# DualBalancedInput.net
KiCad netlist of a schematic drawn in EAGLE
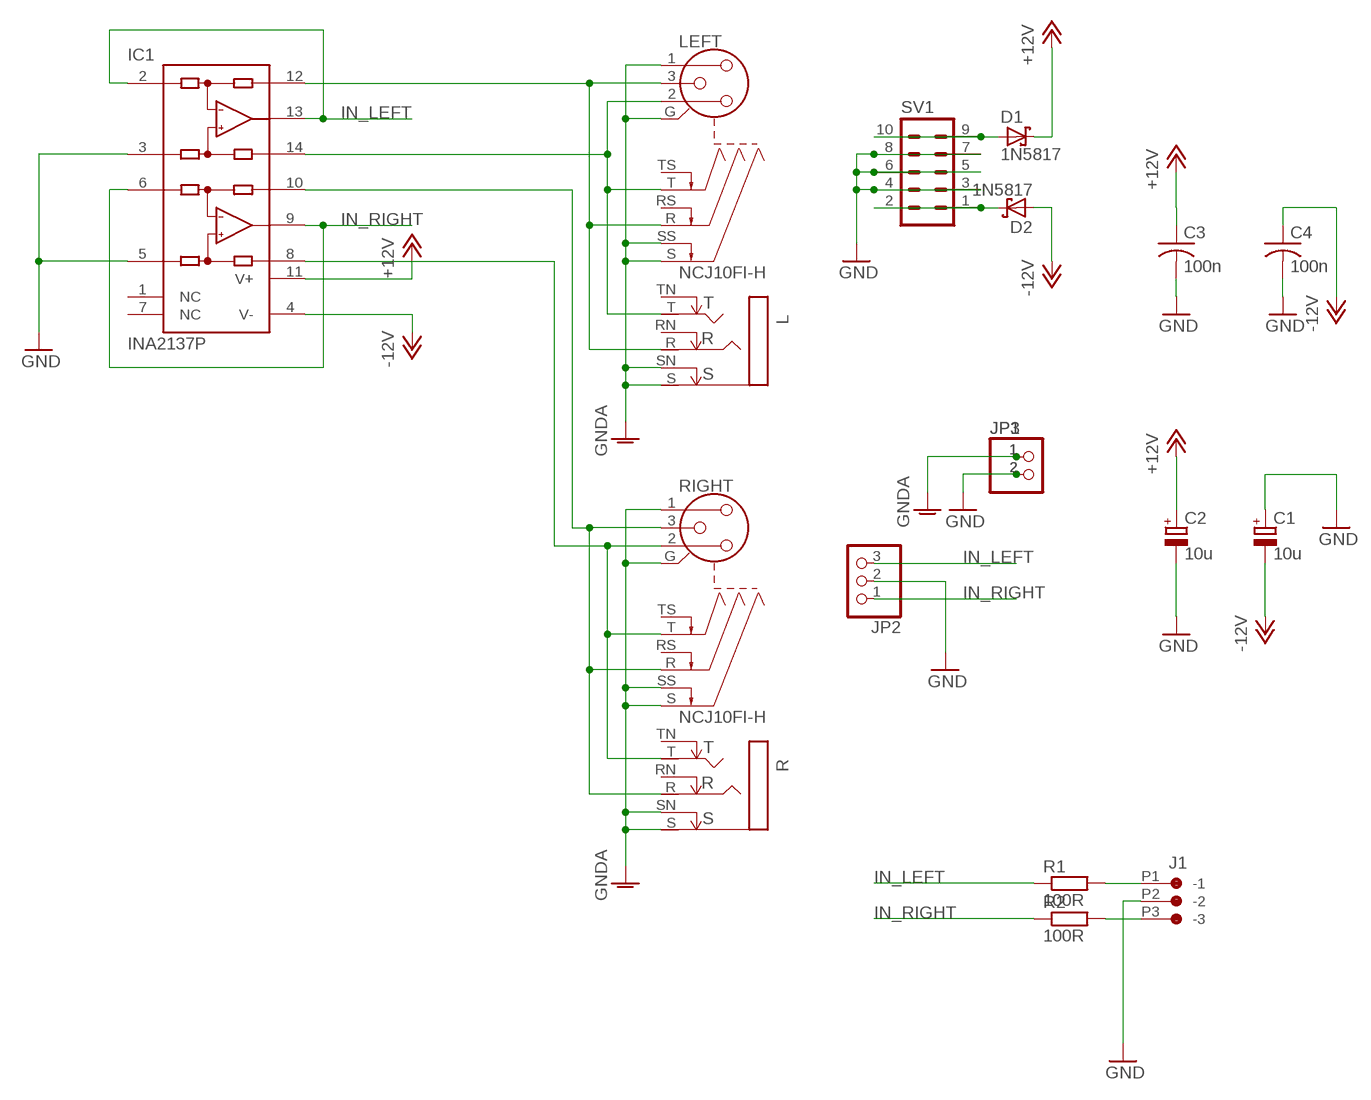
[diagram p0: schematic, sheet 1]

(export (version "E")
  (design (tool "Eeschema 10.0.6"))
  (components
    (comp (ref "C1")
      (value "10u")
      (footprint "eagle-import:E5-6")
      (libsource (lib "eagle-import") (part "CPOL-EUE5-6"))
    )
    (comp (ref "C2")
      (value "10u")
      (footprint "eagle-import:E5-6")
      (libsource (lib "eagle-import") (part "CPOL-EUE5-6"))
    )
    (comp (ref "C3")
      (value "100n")
      (footprint "eagle-import:C050-024X044")
      (libsource (lib "eagle-import") (part "C-US050-024X044"))
    )
    (comp (ref "C4")
      (value "100n")
      (footprint "eagle-import:C050-024X044")
      (libsource (lib "eagle-import") (part "C-US050-024X044"))
    )
    (comp (ref "D1")
      (value "1N5817")
      (footprint "eagle-import:DO41-7.6")
      (libsource (lib "eagle-import") (part "1N5819-B"))
    )
    (comp (ref "D2")
      (value "1N5817")
      (footprint "eagle-import:DO41-7.6")
      (libsource (lib "eagle-import") (part "1N5819-B"))
    )
    (comp (ref "IC1")
      (value "INA2137P")
      (footprint "eagle-import:DIL14")
      (fields (field (name "MF") "TEXAS INSTRUMENT CONNECTORS") (field (name "MPN") "INA2137PA"))
      (libsource (lib "eagle-import") (part "INA2137P"))
    )
    (comp (ref "J1")
      (value "CON-JST_PH_3W")
      (footprint "eagle-import:CON-JST_PH_3W")
      (libsource (lib "eagle-import") (part "CON-JST_PH_3W"))
    )
    (comp (ref "JP1")
      (value "PINHD-1X2")
      (footprint "eagle-import:1X02")
      (libsource (lib "eagle-import") (part "PINHD-1X2"))
    )
    (comp (ref "JP2")
      (value "PINHD-1X3")
      (footprint "eagle-import:1X03")
      (libsource (lib "eagle-import") (part "PINHD-1X3"))
    )
    (comp (ref "JP3")
      (value "PINHD-1X2")
      (footprint "eagle-import:1X02")
      (libsource (lib "eagle-import") (part "PINHD-1X2"))
    )
    (comp (ref "L")
      (value "NEUTRIK_NMJ6HCD2")
      (footprint "eagle-import:NMJ6HCD2")
      (libsource (lib "eagle-import") (part "NEUTRIK_NMJ6HCD2"))
    )
    (comp (ref "LEFT")
      (value "NCJ10FI-H")
      (footprint "eagle-import:NCJ10FI-H")
      (libsource (lib "eagle-import") (part "NCJ10FI-H"))
    )
    (comp (ref "R")
      (value "NEUTRIK_NMJ6HCD2")
      (footprint "eagle-import:NMJ6HCD2")
      (libsource (lib "eagle-import") (part "NEUTRIK_NMJ6HCD2"))
    )
    (comp (ref "R1")
      (value "100R")
      (footprint "eagle-import:0204_7")
      (libsource (lib "eagle-import") (part "R-EU_0204/7"))
    )
    (comp (ref "R2")
      (value "100R")
      (footprint "eagle-import:0204_7")
      (libsource (lib "eagle-import") (part "R-EU_0204/7"))
    )
    (comp (ref "RIGHT")
      (value "NCJ10FI-H")
      (footprint "eagle-import:NCJ10FI-H")
      (libsource (lib "eagle-import") (part "NCJ10FI-H"))
    )
    (comp (ref "SV1")
      (value "MA05-2")
      (footprint "eagle-import:MA05-2")
      (libsource (lib "eagle-import") (part "MA05-2"))
    )
  )
  (nets
    (net (code "1") (name "+12V") (class "Default")
      (node (ref "C2") (pin "+") (pinfunction "+_+") (pintype "passive"))
      (node (ref "C3") (pin "1") (pinfunction "1_1") (pintype "passive"))
      (node (ref "D1") (pin "C") (pinfunction "C_C") (pintype "passive"))
      (node (ref "IC1") (pin "11") (pinfunction "V+_11") (pintype "power_in"))
    )
    (net (code "2") (name "-12V") (class "Default")
      (node (ref "C1") (pin "-") (pinfunction "-_-") (pintype "passive"))
      (node (ref "C4") (pin "1") (pinfunction "1_1") (pintype "passive"))
      (node (ref "D2") (pin "A") (pinfunction "A_A") (pintype "passive"))
      (node (ref "IC1") (pin "4") (pinfunction "V-_4") (pintype "power_in"))
    )
    (net (code "3") (name "/IN_LEFT") (class "Default")
      (node (ref "IC1") (pin "13") (pinfunction "OUTA_13") (pintype "output"))
      (node (ref "IC1") (pin "2") (pinfunction "-INA_2") (pintype "input"))
      (node (ref "JP2") (pin "3") (pinfunction "3_3") (pintype "passive"))
      (node (ref "R1") (pin "1") (pinfunction "1_1") (pintype "passive"))
    )
    (net (code "4") (name "/IN_RIGHT") (class "Default")
      (node (ref "IC1") (pin "6") (pinfunction "-INB_6") (pintype "input"))
      (node (ref "IC1") (pin "9") (pinfunction "OUTB_9") (pintype "output"))
      (node (ref "JP2") (pin "1") (pinfunction "1_1") (pintype "passive"))
      (node (ref "R2") (pin "1") (pinfunction "1_1") (pintype "passive"))
    )
    (net (code "5") (name "GND") (class "Default")
      (node (ref "C1") (pin "+") (pinfunction "+_+") (pintype "passive"))
      (node (ref "C2") (pin "-") (pinfunction "-_-") (pintype "passive"))
      (node (ref "C3") (pin "2") (pinfunction "2_2") (pintype "passive"))
      (node (ref "C4") (pin "2") (pinfunction "2_2") (pintype "passive"))
      (node (ref "IC1") (pin "3") (pinfunction "+INA_3") (pintype "input"))
      (node (ref "IC1") (pin "5") (pinfunction "+INB_5") (pintype "input"))
      (node (ref "J1") (pin "P2") (pinfunction "-2_P2") (pintype "bidirectional"))
      (node (ref "JP1") (pin "2") (pinfunction "2_2") (pintype "passive"))
      (node (ref "JP2") (pin "2") (pinfunction "2_2") (pintype "passive"))
      (node (ref "JP3") (pin "2") (pinfunction "2_2") (pintype "passive"))
      (node (ref "SV1") (pin "3") (pinfunction "3_3") (pintype "passive"))
      (node (ref "SV1") (pin "4") (pinfunction "4_4") (pintype "passive"))
      (node (ref "SV1") (pin "5") (pinfunction "5_5") (pintype "passive"))
      (node (ref "SV1") (pin "6") (pinfunction "6_6") (pintype "passive"))
      (node (ref "SV1") (pin "7") (pinfunction "7_7") (pintype "passive"))
      (node (ref "SV1") (pin "8") (pinfunction "8_8") (pintype "passive"))
    )
    (net (code "6") (name "GNDA") (class "Default")
      (node (ref "JP1") (pin "1") (pinfunction "1_1") (pintype "passive"))
      (node (ref "JP3") (pin "1") (pinfunction "1_1") (pintype "passive"))
      (node (ref "L") (pin "S") (pinfunction "S_S") (pintype "passive"))
      (node (ref "L") (pin "SN") (pinfunction "SN_SN") (pintype "passive"))
      (node (ref "LEFT") (pin "1") (pinfunction "1_1") (pintype "passive"))
      (node (ref "LEFT") (pin "G") (pinfunction "G_G") (pintype "passive"))
      (node (ref "LEFT") (pin "S") (pinfunction "S_S") (pintype "passive"))
      (node (ref "LEFT") (pin "SS") (pinfunction "SS_SS") (pintype "passive"))
      (node (ref "R") (pin "S") (pinfunction "S_S") (pintype "passive"))
      (node (ref "R") (pin "SN") (pinfunction "SN_SN") (pintype "passive"))
      (node (ref "RIGHT") (pin "1") (pinfunction "1_1") (pintype "passive"))
      (node (ref "RIGHT") (pin "G") (pinfunction "G_G") (pintype "passive"))
      (node (ref "RIGHT") (pin "S") (pinfunction "S_S") (pintype "passive"))
      (node (ref "RIGHT") (pin "SS") (pinfunction "SS_SS") (pintype "passive"))
    )
    (net (code "7") (name "Net-(D1-PadA)") (class "Default")
      (node (ref "D1") (pin "A") (pinfunction "A_A") (pintype "passive"))
      (node (ref "SV1") (pin "10") (pinfunction "10_10") (pintype "passive"))
      (node (ref "SV1") (pin "9") (pinfunction "9_9") (pintype "passive"))
    )
    (net (code "8") (name "Net-(D2-PadC)") (class "Default")
      (node (ref "D2") (pin "C") (pinfunction "C_C") (pintype "passive"))
      (node (ref "SV1") (pin "1") (pinfunction "1_1") (pintype "passive"))
      (node (ref "SV1") (pin "2") (pinfunction "2_2") (pintype "passive"))
    )
    (net (code "9") (name "Net-(IC1-REFA)") (class "Default")
      (node (ref "IC1") (pin "14") (pinfunction "REFA_14") (pintype "passive"))
      (node (ref "L") (pin "T") (pinfunction "T_T") (pintype "passive"))
      (node (ref "LEFT") (pin "2") (pinfunction "2_2") (pintype "passive"))
      (node (ref "LEFT") (pin "T") (pinfunction "T_T") (pintype "passive"))
    )
    (net (code "10") (name "Net-(IC1-REFB)") (class "Default")
      (node (ref "IC1") (pin "8") (pinfunction "REFB_8") (pintype "passive"))
      (node (ref "R") (pin "T") (pinfunction "T_T") (pintype "passive"))
      (node (ref "RIGHT") (pin "2") (pinfunction "2_2") (pintype "passive"))
      (node (ref "RIGHT") (pin "T") (pinfunction "T_T") (pintype "passive"))
    )
    (net (code "11") (name "Net-(IC1-SENSEA)") (class "Default")
      (node (ref "IC1") (pin "12") (pinfunction "SENSEA_12") (pintype "passive"))
      (node (ref "L") (pin "R") (pinfunction "R_R") (pintype "passive"))
      (node (ref "LEFT") (pin "3") (pinfunction "3_3") (pintype "passive"))
      (node (ref "LEFT") (pin "R") (pinfunction "R_R") (pintype "passive"))
    )
    (net (code "12") (name "Net-(IC1-SENSEB)") (class "Default")
      (node (ref "IC1") (pin "10") (pinfunction "SENSEB_10") (pintype "passive"))
      (node (ref "R") (pin "R") (pinfunction "R_R") (pintype "passive"))
      (node (ref "RIGHT") (pin "3") (pinfunction "3_3") (pintype "passive"))
      (node (ref "RIGHT") (pin "R") (pinfunction "R_R") (pintype "passive"))
    )
    (net (code "13") (name "Net-(J1--1)") (class "Default")
      (node (ref "J1") (pin "P1") (pinfunction "-1_P1") (pintype "bidirectional"))
      (node (ref "R1") (pin "2") (pinfunction "2_2") (pintype "passive"))
    )
    (net (code "14") (name "Net-(J1--3)") (class "Default")
      (node (ref "J1") (pin "P3") (pinfunction "-3_P3") (pintype "bidirectional"))
      (node (ref "R2") (pin "2") (pinfunction "2_2") (pintype "passive"))
    )
    (net (code "15") (name "unconnected-(IC1-NC-Pad1)") (class "Default")
      (node (ref "IC1") (pin "1") (pinfunction "NC_1") (pintype "no_connect"))
    )
    (net (code "16") (name "unconnected-(IC1-NC-Pad7)") (class "Default")
      (node (ref "IC1") (pin "7") (pinfunction "NC_7") (pintype "no_connect"))
    )
    (net (code "17") (name "unconnected-(L-PadRN)") (class "Default")
      (node (ref "L") (pin "RN") (pinfunction "RN_RN") (pintype "passive"))
    )
    (net (code "18") (name "unconnected-(L-PadTN)") (class "Default")
      (node (ref "L") (pin "TN") (pinfunction "TN_TN") (pintype "passive"))
    )
    (net (code "19") (name "unconnected-(LEFT-PadRS)") (class "Default")
      (node (ref "LEFT") (pin "RS") (pinfunction "RS_RS") (pintype "passive"))
    )
    (net (code "20") (name "unconnected-(LEFT-PadTS)") (class "Default")
      (node (ref "LEFT") (pin "TS") (pinfunction "TS_TS") (pintype "passive"))
    )
    (net (code "21") (name "unconnected-(R-PadRN)") (class "Default")
      (node (ref "R") (pin "RN") (pinfunction "RN_RN") (pintype "passive"))
    )
    (net (code "22") (name "unconnected-(R-PadTN)") (class "Default")
      (node (ref "R") (pin "TN") (pinfunction "TN_TN") (pintype "passive"))
    )
    (net (code "23") (name "unconnected-(RIGHT-PadRS)") (class "Default")
      (node (ref "RIGHT") (pin "RS") (pinfunction "RS_RS") (pintype "passive"))
    )
    (net (code "24") (name "unconnected-(RIGHT-PadTS)") (class "Default")
      (node (ref "RIGHT") (pin "TS") (pinfunction "TS_TS") (pintype "passive"))
    )
  )
)
